# ADCduinoModule.net
KiCad netlist of a schematic drawn in Altium Designer
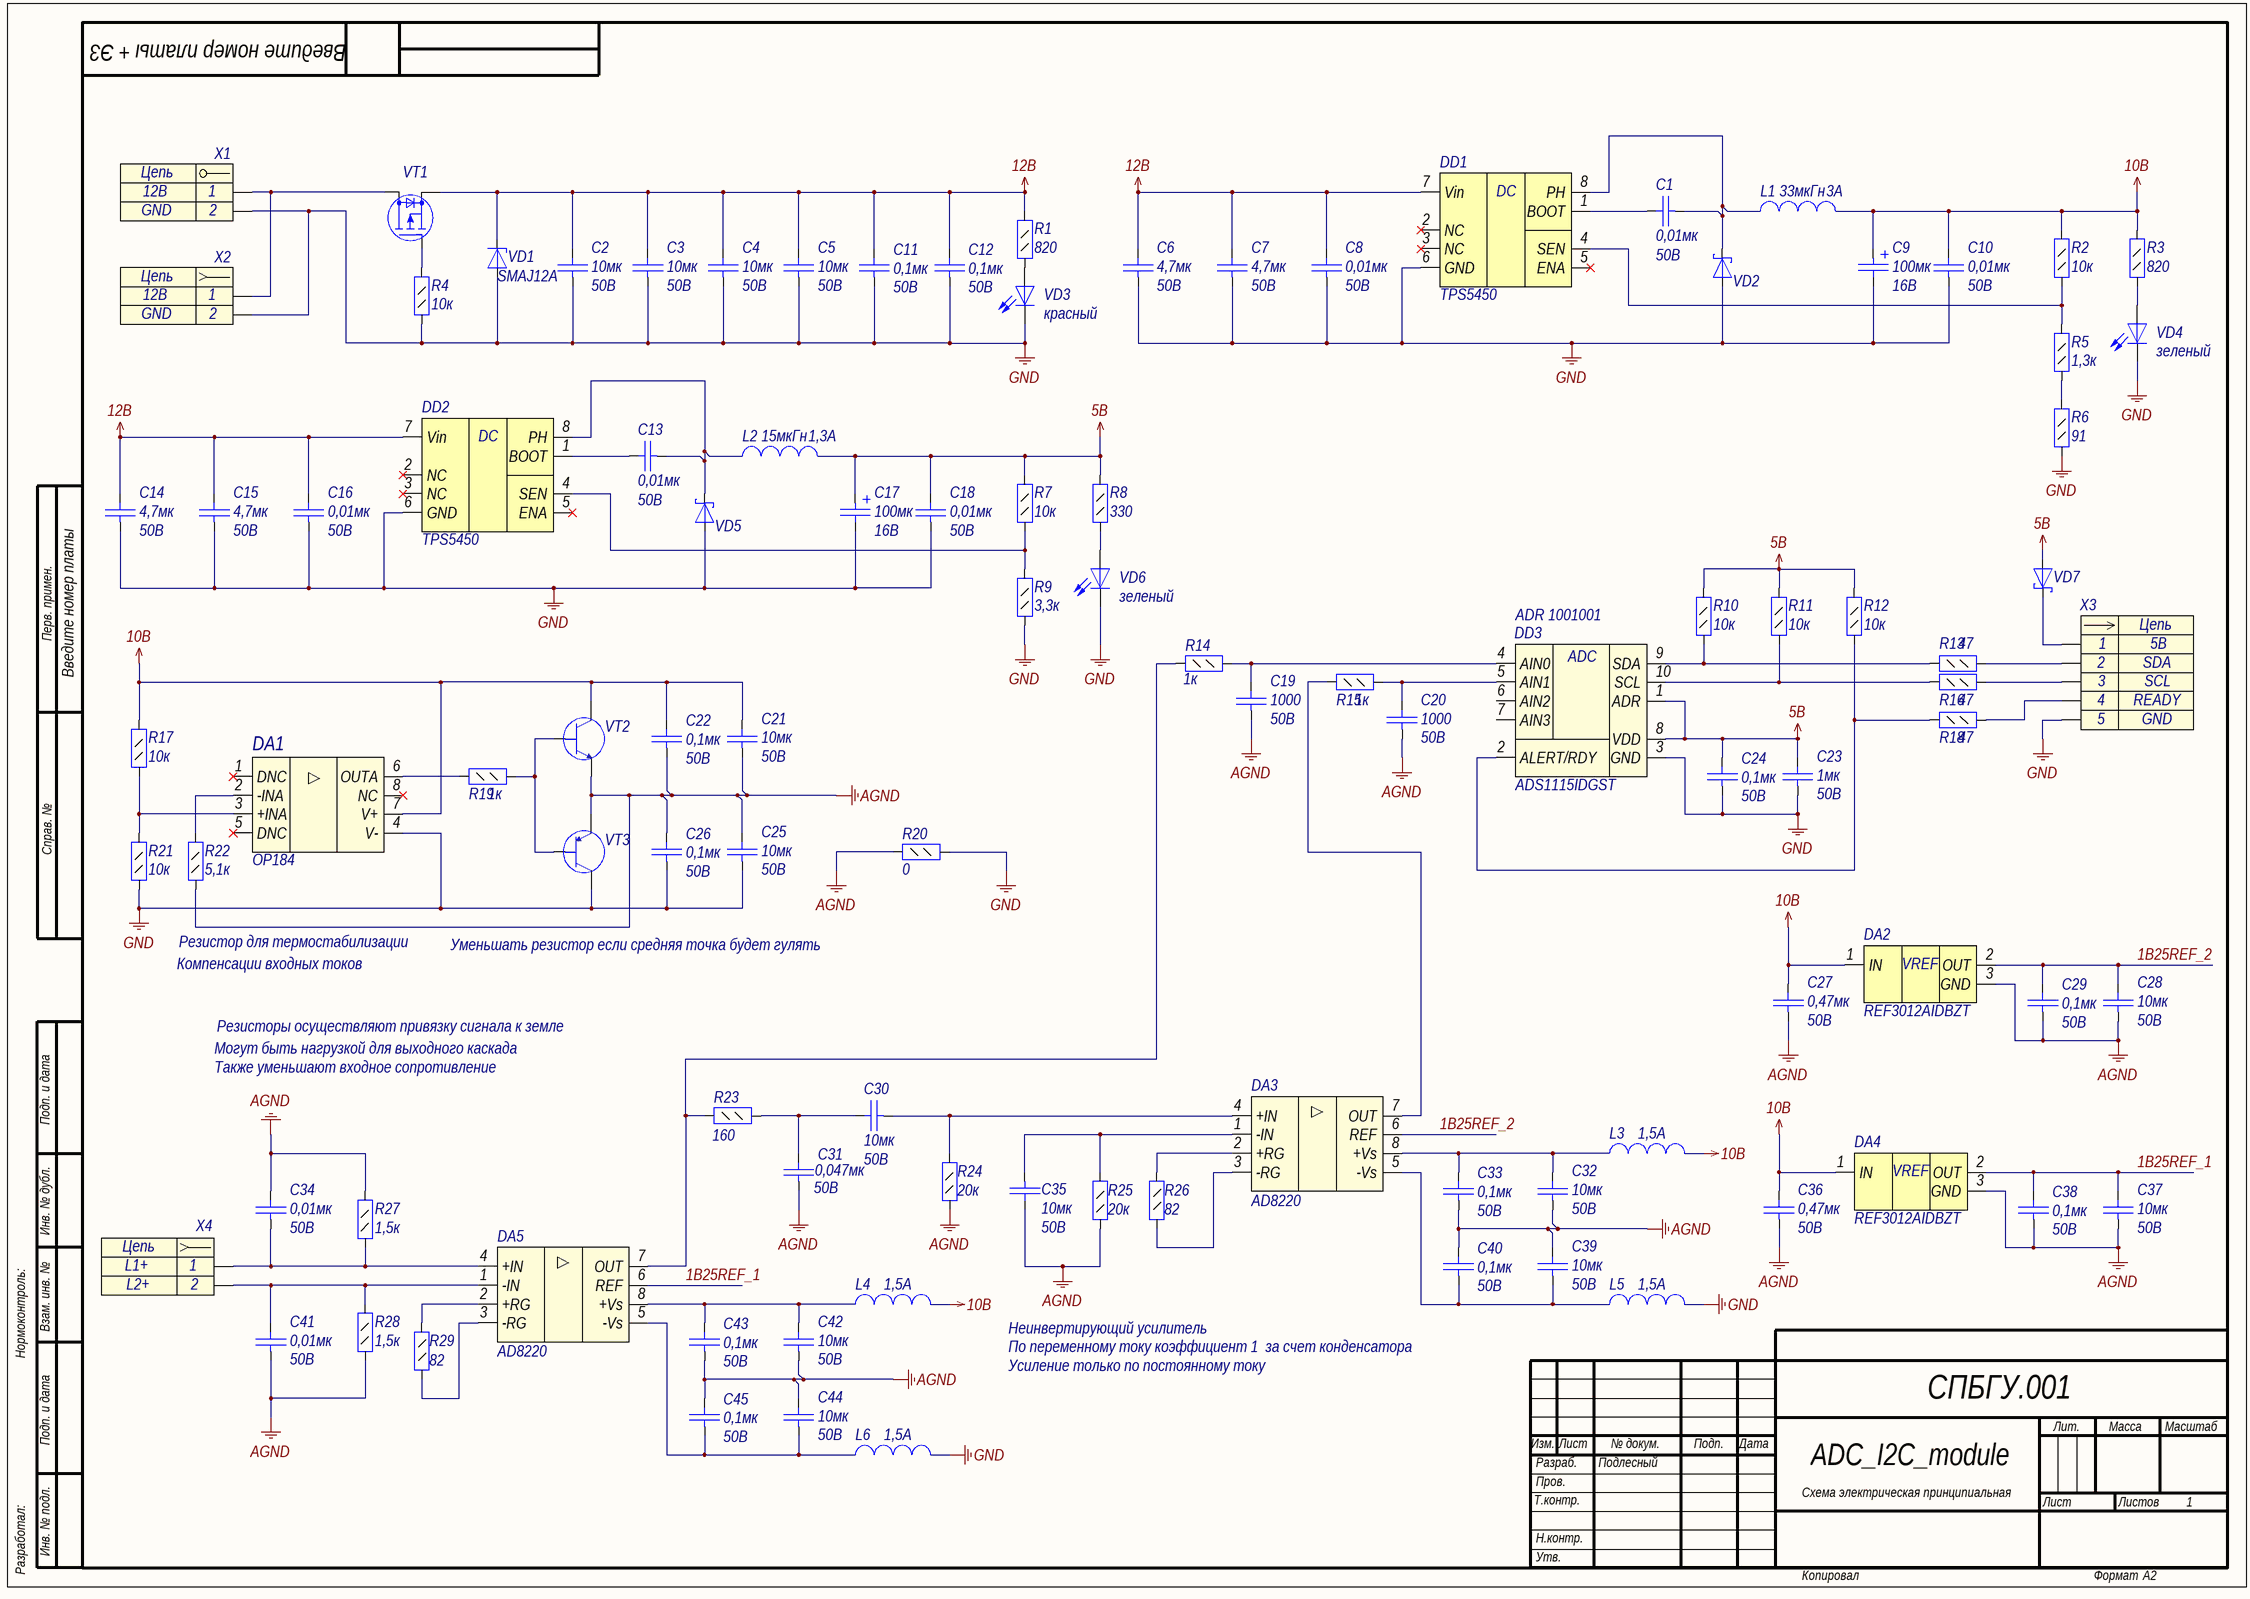
[diagram p0: ADCduinoModule.SchDoc]

(export (version "E")
  (design (tool "Eeschema 10.0.6"))
  (components
    (comp (ref "C1")
      (value "0,01мк")
      (footprint "C0805")
      (description "Конденсатор")
      (fields
        (field (name "VOLTAGE") "50B")
        (field (name "PART NUMBER") "GRM216R71H103K")
        (field (name "Comment") "Capacitor")
      )
      (libsource (lib "MOP44") (part "Capacitor"))
    )
    (comp (ref "C2")
      (value "10мк")
      (footprint "C1210")
      (description "Конденсатор")
      (fields
        (field (name "VOLTAGE") "50В")
        (field (name "PART NUMBER") "GRM32ER71H106K")
        (field (name "Comment") "Capacitor")
      )
      (libsource (lib "MOP44") (part "Capacitor"))
    )
    (comp (ref "C3")
      (value "10мк")
      (footprint "C1210")
      (description "Конденсатор")
      (fields
        (field (name "VOLTAGE") "50В")
        (field (name "PART NUMBER") "GRM32ER71H106K")
        (field (name "Comment") "Capacitor")
      )
      (libsource (lib "MOP44") (part "Capacitor"))
    )
    (comp (ref "C4")
      (value "10мк")
      (footprint "C1210")
      (description "Конденсатор")
      (fields
        (field (name "VOLTAGE") "50В")
        (field (name "PART NUMBER") "GRM32ER71H106K")
        (field (name "Comment") "Capacitor")
      )
      (libsource (lib "MOP44") (part "Capacitor"))
    )
    (comp (ref "C5")
      (value "10мк")
      (footprint "C1210")
      (description "Конденсатор")
      (fields
        (field (name "VOLTAGE") "50В")
        (field (name "PART NUMBER") "GRM32ER71H106K")
        (field (name "Comment") "Capacitor")
      )
      (libsource (lib "MOP44") (part "Capacitor"))
    )
    (comp (ref "C6")
      (value "4,7мк")
      (footprint "C1206")
      (description "Конденсатор")
      (fields
        (field (name "VOLTAGE") "50В")
        (field (name "PART NUMBER") "GRM31CR71H475KA12L")
        (field (name "Comment") "Capacitor")
      )
      (libsource (lib "MOP44") (part "Capacitor"))
    )
    (comp (ref "C7")
      (value "4,7мк")
      (footprint "C1206")
      (description "Конденсатор")
      (fields
        (field (name "VOLTAGE") "50В")
        (field (name "PART NUMBER") "GRM31CR71H475KA12L")
        (field (name "Comment") "Capacitor")
      )
      (libsource (lib "MOP44") (part "Capacitor"))
    )
    (comp (ref "C8")
      (value "0,01мк")
      (footprint "C0805")
      (description "Конденсатор")
      (fields
        (field (name "VOLTAGE") "50B")
        (field (name "PART NUMBER") "GRM216R71H103K")
        (field (name "Comment") "Capacitor")
      )
      (libsource (lib "MOP44") (part "Capacitor"))
    )
    (comp (ref "C9")
      (value "100мк")
      (footprint "TANTAL CASE D")
      (description "Конденсатор полярный")
      (fields
        (field (name "VOLTAGE") "16В")
        (field (name "PART NUMBER") "293D107X9016D2TE3")
        (field (name "Comment") "Capacitor_pol")
      )
      (libsource (lib "MOP44") (part "Capacitor_pol"))
    )
    (comp (ref "C10")
      (value "0,01мк")
      (footprint "C0805")
      (description "Конденсатор")
      (fields
        (field (name "VOLTAGE") "50B")
        (field (name "PART NUMBER") "GRM216R71H103K")
        (field (name "Comment") "Capacitor")
      )
      (libsource (lib "MOP44") (part "Capacitor"))
    )
    (comp (ref "C11")
      (value "0,1мк")
      (footprint "C0805")
      (description "Конденсатор")
      (fields
        (field (name "VOLTAGE") "50B")
        (field (name "PART NUMBER") "GRM21BR71H104K**")
        (field (name "Comment") "Capacitor")
      )
      (libsource (lib "MOP44") (part "Capacitor"))
    )
    (comp (ref "C12")
      (value "0,1мк")
      (footprint "C0805")
      (description "Конденсатор")
      (fields
        (field (name "VOLTAGE") "50B")
        (field (name "PART NUMBER") "GRM21BR71H104K**")
        (field (name "Comment") "Capacitor")
      )
      (libsource (lib "MOP44") (part "Capacitor"))
    )
    (comp (ref "C13")
      (value "0,01мк")
      (footprint "C0805")
      (description "Конденсатор")
      (fields
        (field (name "VOLTAGE") "50B")
        (field (name "PART NUMBER") "GRM216R71H103K")
        (field (name "Comment") "Capacitor")
      )
      (libsource (lib "MOP44") (part "Capacitor"))
    )
    (comp (ref "C14")
      (value "4,7мк")
      (footprint "C1206")
      (description "Конденсатор")
      (fields
        (field (name "VOLTAGE") "50В")
        (field (name "PART NUMBER") "GRM31CR71H475KA12L")
        (field (name "Comment") "Capacitor")
      )
      (libsource (lib "MOP44") (part "Capacitor"))
    )
    (comp (ref "C15")
      (value "4,7мк")
      (footprint "C1206")
      (description "Конденсатор")
      (fields
        (field (name "VOLTAGE") "50В")
        (field (name "PART NUMBER") "GRM31CR71H475KA12L")
        (field (name "Comment") "Capacitor")
      )
      (libsource (lib "MOP44") (part "Capacitor"))
    )
    (comp (ref "C16")
      (value "0,01мк")
      (footprint "C0805")
      (description "Конденсатор")
      (fields
        (field (name "VOLTAGE") "50B")
        (field (name "PART NUMBER") "GRM216R71H103K")
        (field (name "Comment") "Capacitor")
      )
      (libsource (lib "MOP44") (part "Capacitor"))
    )
    (comp (ref "C17")
      (value "100мк")
      (footprint "TANTAL CASE D")
      (description "Конденсатор полярный")
      (fields
        (field (name "VOLTAGE") "16В")
        (field (name "PART NUMBER") "293D107X9016D2TE3")
        (field (name "Comment") "Capacitor_pol")
      )
      (libsource (lib "MOP44") (part "Capacitor_pol"))
    )
    (comp (ref "C18")
      (value "0,01мк")
      (footprint "C0805")
      (description "Конденсатор")
      (fields
        (field (name "VOLTAGE") "50B")
        (field (name "PART NUMBER") "GRM216R71H103K")
        (field (name "Comment") "Capacitor")
      )
      (libsource (lib "MOP44") (part "Capacitor"))
    )
    (comp (ref "C19")
      (value "1000")
      (footprint "C0805")
      (description "Конденсатор")
      (fields
        (field (name "VOLTAGE") "50В")
        (field (name "PART NUMBER") "GRM216R71H102K*")
        (field (name "Comment") "Capacitor")
      )
      (libsource (lib "MOP44") (part "Capacitor"))
    )
    (comp (ref "C20")
      (value "1000")
      (footprint "C0805")
      (description "Конденсатор")
      (fields
        (field (name "VOLTAGE") "50В")
        (field (name "PART NUMBER") "GRM216R71H102K*")
        (field (name "Comment") "Capacitor")
      )
      (libsource (lib "MOP44") (part "Capacitor"))
    )
    (comp (ref "C21")
      (value "10мк")
      (footprint "C1210")
      (description "Конденсатор")
      (fields
        (field (name "VOLTAGE") "50В")
        (field (name "PART NUMBER") "GRM32ER71H106K")
        (field (name "Comment") "Capacitor")
      )
      (libsource (lib "MOP44") (part "Capacitor"))
    )
    (comp (ref "C22")
      (value "0,1мк")
      (footprint "C0805")
      (description "Конденсатор")
      (fields
        (field (name "VOLTAGE") "50B")
        (field (name "PART NUMBER") "GRM21BR71H104K**")
        (field (name "Comment") "Capacitor")
      )
      (libsource (lib "MOP44") (part "Capacitor"))
    )
    (comp (ref "C23")
      (value "1мк")
      (footprint "C0805")
      (description "Конденсатор")
      (fields
        (field (name "VOLTAGE") "50B")
        (field (name "PART NUMBER") "GRM21BR71H105K")
        (field (name "Comment") "Capacitor")
      )
      (libsource (lib "MOP44") (part "Capacitor"))
    )
    (comp (ref "C24")
      (value "0,1мк")
      (footprint "C0805")
      (description "Конденсатор")
      (fields
        (field (name "VOLTAGE") "50B")
        (field (name "PART NUMBER") "GRM21BR71H104K**")
        (field (name "Comment") "Capacitor")
      )
      (libsource (lib "MOP44") (part "Capacitor"))
    )
    (comp (ref "C25")
      (value "10мк")
      (footprint "C1210")
      (description "Конденсатор")
      (fields
        (field (name "VOLTAGE") "50В")
        (field (name "PART NUMBER") "GRM32ER71H106K")
        (field (name "Comment") "Capacitor")
      )
      (libsource (lib "MOP44") (part "Capacitor"))
    )
    (comp (ref "C26")
      (value "0,1мк")
      (footprint "C0805")
      (description "Конденсатор")
      (fields
        (field (name "VOLTAGE") "50B")
        (field (name "PART NUMBER") "GRM21BR71H104K**")
        (field (name "Comment") "Capacitor")
      )
      (libsource (lib "MOP44") (part "Capacitor"))
    )
    (comp (ref "C27")
      (value "0,47мк")
      (footprint "C0805")
      (description "Конденсатор")
      (fields
        (field (name "VOLTAGE") "50B")
        (field (name "PART NUMBER") "GRM219R71C474K")
        (field (name "Comment") "Capacitor")
      )
      (libsource (lib "MOP44") (part "Capacitor"))
    )
    (comp (ref "C28")
      (value "10мк")
      (footprint "C1210")
      (description "Конденсатор")
      (fields
        (field (name "VOLTAGE") "50В")
        (field (name "PART NUMBER") "GRM32ER71H106K")
        (field (name "Comment") "Capacitor")
      )
      (libsource (lib "MOP44") (part "Capacitor"))
    )
    (comp (ref "C29")
      (value "0,1мк")
      (footprint "C0805")
      (description "Конденсатор")
      (fields
        (field (name "VOLTAGE") "50B")
        (field (name "PART NUMBER") "GRM21BR71H104K**")
        (field (name "Comment") "Capacitor")
      )
      (libsource (lib "MOP44") (part "Capacitor"))
    )
    (comp (ref "C30")
      (value "10мк")
      (footprint "C1210")
      (description "Конденсатор")
      (fields
        (field (name "VOLTAGE") "50В")
        (field (name "PART NUMBER") "GRM32ER71H106K")
        (field (name "Comment") "Capacitor")
      )
      (libsource (lib "MOP44") (part "Capacitor"))
    )
    (comp (ref "C31")
      (value "0,047мк")
      (footprint "C0805")
      (description "Конденсатор")
      (fields
        (field (name "VOLTAGE") "50B")
        (field (name "PART NUMBER") "GRM21BR71H473K")
        (field (name "Comment") "Capacitor")
      )
      (libsource (lib "MOP44") (part "Capacitor"))
    )
    (comp (ref "C32")
      (value "10мк")
      (footprint "C1210")
      (description "Конденсатор")
      (fields
        (field (name "VOLTAGE") "50В")
        (field (name "PART NUMBER") "GRM32ER71H106K")
        (field (name "Comment") "Capacitor")
      )
      (libsource (lib "MOP44") (part "Capacitor"))
    )
    (comp (ref "C33")
      (value "0,1мк")
      (footprint "C0805")
      (description "Конденсатор")
      (fields
        (field (name "VOLTAGE") "50B")
        (field (name "PART NUMBER") "GRM21BR71H104K**")
        (field (name "Comment") "Capacitor")
      )
      (libsource (lib "MOP44") (part "Capacitor"))
    )
    (comp (ref "C34")
      (value "0,01мк")
      (footprint "C0805")
      (description "Конденсатор")
      (fields
        (field (name "VOLTAGE") "50B")
        (field (name "PART NUMBER") "GRM216R71H103K")
        (field (name "Comment") "Capacitor")
      )
      (libsource (lib "MOP44") (part "Capacitor"))
    )
    (comp (ref "C35")
      (value "10мк")
      (footprint "C1210")
      (description "Конденсатор")
      (fields
        (field (name "VOLTAGE") "50В")
        (field (name "PART NUMBER") "GRM32ER71H106K")
        (field (name "Comment") "Capacitor")
      )
      (libsource (lib "MOP44") (part "Capacitor"))
    )
    (comp (ref "C36")
      (value "0,47мк")
      (footprint "C0805")
      (description "Конденсатор")
      (fields
        (field (name "VOLTAGE") "50B")
        (field (name "PART NUMBER") "GRM219R71C474K")
        (field (name "Comment") "Capacitor")
      )
      (libsource (lib "MOP44") (part "Capacitor"))
    )
    (comp (ref "C37")
      (value "10мк")
      (footprint "C1210")
      (description "Конденсатор")
      (fields
        (field (name "VOLTAGE") "50В")
        (field (name "PART NUMBER") "GRM32ER71H106K")
        (field (name "Comment") "Capacitor")
      )
      (libsource (lib "MOP44") (part "Capacitor"))
    )
    (comp (ref "C38")
      (value "0,1мк")
      (footprint "C0805")
      (description "Конденсатор")
      (fields
        (field (name "VOLTAGE") "50B")
        (field (name "PART NUMBER") "GRM21BR71H104K**")
        (field (name "Comment") "Capacitor")
      )
      (libsource (lib "MOP44") (part "Capacitor"))
    )
    (comp (ref "C39")
      (value "10мк")
      (footprint "C1210")
      (description "Конденсатор")
      (fields
        (field (name "VOLTAGE") "50В")
        (field (name "PART NUMBER") "GRM32ER71H106K")
        (field (name "Comment") "Capacitor")
      )
      (libsource (lib "MOP44") (part "Capacitor"))
    )
    (comp (ref "C40")
      (value "0,1мк")
      (footprint "C0805")
      (description "Конденсатор")
      (fields
        (field (name "VOLTAGE") "50B")
        (field (name "PART NUMBER") "GRM21BR71H104K**")
        (field (name "Comment") "Capacitor")
      )
      (libsource (lib "MOP44") (part "Capacitor"))
    )
    (comp (ref "C41")
      (value "0,01мк")
      (footprint "C0805")
      (description "Конденсатор")
      (fields
        (field (name "VOLTAGE") "50B")
        (field (name "PART NUMBER") "GRM216R71H103K")
        (field (name "Comment") "Capacitor")
      )
      (libsource (lib "MOP44") (part "Capacitor"))
    )
    (comp (ref "C42")
      (value "10мк")
      (footprint "C1210")
      (description "Конденсатор")
      (fields
        (field (name "VOLTAGE") "50В")
        (field (name "PART NUMBER") "GRM32ER71H106K")
        (field (name "Comment") "Capacitor")
      )
      (libsource (lib "MOP44") (part "Capacitor"))
    )
    (comp (ref "C43")
      (value "0,1мк")
      (footprint "C0805")
      (description "Конденсатор")
      (fields
        (field (name "VOLTAGE") "50B")
        (field (name "PART NUMBER") "GRM21BR71H104K**")
        (field (name "Comment") "Capacitor")
      )
      (libsource (lib "MOP44") (part "Capacitor"))
    )
    (comp (ref "C44")
      (value "10мк")
      (footprint "C1210")
      (description "Конденсатор")
      (fields
        (field (name "VOLTAGE") "50В")
        (field (name "PART NUMBER") "GRM32ER71H106K")
        (field (name "Comment") "Capacitor")
      )
      (libsource (lib "MOP44") (part "Capacitor"))
    )
    (comp (ref "C45")
      (value "0,1мк")
      (footprint "C0805")
      (description "Конденсатор")
      (fields
        (field (name "VOLTAGE") "50B")
        (field (name "PART NUMBER") "GRM21BR71H104K**")
        (field (name "Comment") "Capacitor")
      )
      (libsource (lib "MOP44") (part "Capacitor"))
    )
    (comp (ref "DA1")
      (value "OP184")
      (footprint "SO8")
      (description "Precision Rail-to-Rail\r\nInput and Output Operational Amplifiers")
      (fields (field (name "PART NUMBER") "OP184ESZ"))
      (libsource (lib "MOP44") (part "OP184"))
    )
    (comp (ref "DA2")
      (value "REF30xx")
      (footprint "SOT23-3")
      (description "CMOS Voltage Reference")
      (fields (field (name "PART NUMBER") "REF3012AIDBZT") (field (name "MANUFACTURER") "Texas Instruments"))
      (libsource (lib "MOP44") (part "REF30xx"))
    )
    (comp (ref "DA3")
      (value "AD8220")
      (footprint "MSOP8")
      (description "JFET Input Instrumentation Amplifier")
      (fields (field (name "PART NUMBER") "AD8220ARMZ"))
      (libsource (lib "MOP44") (part "AD8220"))
    )
    (comp (ref "DA4")
      (value "REF30xx")
      (footprint "SOT23-3")
      (description "CMOS Voltage Reference")
      (fields (field (name "PART NUMBER") "REF3012AIDBZT") (field (name "MANUFACTURER") "Texas Instruments"))
      (libsource (lib "MOP44") (part "REF30xx"))
    )
    (comp (ref "DA5")
      (value "AD8220")
      (footprint "MSOP8")
      (description "JFET Input Instrumentation Amplifier")
      (fields (field (name "PART NUMBER") "AD8220ARMZ"))
      (libsource (lib "MOP44") (part "AD8220"))
    )
    (comp (ref "DD1")
      (value "TPS5450")
      (footprint "SO Powerpad8")
      (description "5-A, Wide Input Range, Step-Down Converter")
      (fields (field (name "MANUFACTURER") "Texas Instruments"))
      (libsource (lib "MOP44") (part "TPS5450"))
    )
    (comp (ref "DD2")
      (value "TPS5450")
      (footprint "SO Powerpad8")
      (description "5-A, Wide Input Range, Step-Down Converter")
      (fields (field (name "MANUFACTURER") "Texas Instruments"))
      (libsource (lib "MOP44") (part "TPS5450"))
    )
    (comp (ref "DD3")
      (value "ADS1115IDGST")
      (footprint "MSOP10")
      (description "Ultra-Small, Low-Power, 16-Bit  Analog-to-Digital Converter with Internal Reference")
      (libsource (lib "MOP44") (part "ADS1115IDGST"))
    )
    (comp (ref "L1")
      (value "33мкГн")
      (footprint "IND_12.8x12.8")
      (description "EMI Suppression Filter")
      (fields
        (field (name "RATED CURRENT") "3A")
        (field (name "PART NUMBER") "B82477G4333M000")
        (field (name "Comment") "Inductor")
      )
      (libsource (lib "MOP44") (part "Inductor"))
    )
    (comp (ref "L2")
      (value "15мкГн")
      (footprint "SDR0604")
      (description "EMI Suppression Filter")
      (fields
        (field (name "RATED CURRENT") "1,3A")
        (field (name "PART NUMBER") "SDR0604- 150YL")
        (field (name "Comment") "Inductor")
      )
      (libsource (lib "MOP44") (part "Inductor"))
    )
    (comp (ref "L3")
      (value "Inductor")
      (footprint "L0603")
      (description "EMI Suppression Filter")
      (fields (field (name "RATED CURRENT") "1,5A") (field (name "PART NUMBER") "BLM18PG181SN1D"))
      (libsource (lib "MOP44") (part "Inductor"))
    )
    (comp (ref "L4")
      (value "Inductor")
      (footprint "L0603")
      (description "EMI Suppression Filter")
      (fields (field (name "RATED CURRENT") "1,5A") (field (name "PART NUMBER") "BLM18PG181SN1D"))
      (libsource (lib "MOP44") (part "Inductor"))
    )
    (comp (ref "L5")
      (value "Inductor")
      (footprint "L0603")
      (description "EMI Suppression Filter")
      (fields (field (name "RATED CURRENT") "1,5A") (field (name "PART NUMBER") "BLM18PG181SN1D"))
      (libsource (lib "MOP44") (part "Inductor"))
    )
    (comp (ref "L6")
      (value "Inductor")
      (footprint "L0603")
      (description "EMI Suppression Filter")
      (fields (field (name "RATED CURRENT") "1,5A") (field (name "PART NUMBER") "BLM18PG181SN1D"))
      (libsource (lib "MOP44") (part "Inductor"))
    )
    (comp (ref "R1")
      (value "820")
      (footprint "R0805")
      (description "Резистор")
      (fields (field (name "PART NUMBER") "RC0805FR-07820RL") (field (name "POWER") "0,125Вт"))
      (libsource (lib "MOP44") (part "Resistor_0,125Вт"))
    )
    (comp (ref "R2")
      (value "10к")
      (footprint "R0805")
      (description "Резистор")
      (fields (field (name "PART NUMBER") "RC0805FR-0710KL") (field (name "POWER") "0,125Вт"))
      (libsource (lib "MOP44") (part "Resistor_0,125Вт"))
    )
    (comp (ref "R3")
      (value "820")
      (footprint "R0805")
      (description "Резистор")
      (fields (field (name "PART NUMBER") "RC0805FR-07820RL") (field (name "POWER") "0,125Вт"))
      (libsource (lib "MOP44") (part "Resistor_0,125Вт"))
    )
    (comp (ref "R4")
      (value "10к")
      (footprint "R0805")
      (description "Резистор")
      (fields (field (name "PART NUMBER") "RC0805FR-0710KL") (field (name "POWER") "0,125Вт"))
      (libsource (lib "MOP44") (part "Resistor_0,125Вт"))
    )
    (comp (ref "R5")
      (value "1,3к")
      (footprint "R0805")
      (description "Резистор")
      (fields (field (name "PART NUMBER") "RC0805FR-071K3") (field (name "POWER") "0,125Вт"))
      (libsource (lib "MOP44") (part "Resistor_0,125Вт"))
    )
    (comp (ref "R6")
      (value "91")
      (footprint "R0805")
      (description "Резистор")
      (fields (field (name "PART NUMBER") "RC0805FR-0791RL") (field (name "POWER") "0,125Вт"))
      (libsource (lib "MOP44") (part "Resistor_0,125Вт"))
    )
    (comp (ref "R7")
      (value "10к")
      (footprint "R0805")
      (description "Резистор")
      (fields (field (name "PART NUMBER") "RC0805FR-0710KL") (field (name "POWER") "0,125Вт"))
      (libsource (lib "MOP44") (part "Resistor_0,125Вт"))
    )
    (comp (ref "R8")
      (value "330")
      (footprint "R0805")
      (description "Резистор")
      (fields (field (name "PART NUMBER") "RC0805FR-07330RL") (field (name "POWER") "0,125Вт"))
      (libsource (lib "MOP44") (part "Resistor_0,125Вт"))
    )
    (comp (ref "R9")
      (value "3,3к")
      (footprint "R0805")
      (description "Резистор")
      (fields (field (name "PART NUMBER") "RC0805FR-072K3") (field (name "POWER") "0,125Вт"))
      (libsource (lib "MOP44") (part "Resistor_0,125Вт"))
    )
    (comp (ref "R10")
      (value "10к")
      (footprint "R0805")
      (description "Резистор")
      (fields (field (name "PART NUMBER") "RC0805FR-0710KL") (field (name "POWER") "0,125Вт"))
      (libsource (lib "MOP44") (part "Resistor_0,125Вт"))
    )
    (comp (ref "R11")
      (value "10к")
      (footprint "R0805")
      (description "Резистор")
      (fields (field (name "PART NUMBER") "RC0805FR-0710KL") (field (name "POWER") "0,125Вт"))
      (libsource (lib "MOP44") (part "Resistor_0,125Вт"))
    )
    (comp (ref "R12")
      (value "10к")
      (footprint "R0805")
      (description "Резистор")
      (fields (field (name "PART NUMBER") "RC0805FR-0710KL") (field (name "POWER") "0,125Вт"))
      (libsource (lib "MOP44") (part "Resistor_0,125Вт"))
    )
    (comp (ref "R13")
      (value "47")
      (footprint "R0805")
      (description "Резистор")
      (fields (field (name "PART NUMBER") "RC0805FR-0747RL") (field (name "POWER") "0,125Вт"))
      (libsource (lib "") (part "Resistor_0,125Вт_1"))
    )
    (comp (ref "R14")
      (value "1к")
      (footprint "R0805")
      (description "Резистор")
      (fields (field (name "PART NUMBER") "RC0805FR-071KL") (field (name "POWER") "0,125Вт"))
      (libsource (lib "") (part "Resistor_0,125Вт_1"))
    )
    (comp (ref "R15")
      (value "1к")
      (footprint "R0805")
      (description "Резистор")
      (fields (field (name "PART NUMBER") "RC0805FR-071KL") (field (name "POWER") "0,125Вт"))
      (libsource (lib "") (part "Resistor_0,125Вт_1"))
    )
    (comp (ref "R16")
      (value "47")
      (footprint "R0805")
      (description "Резистор")
      (fields (field (name "PART NUMBER") "RC0805FR-0747RL") (field (name "POWER") "0,125Вт"))
      (libsource (lib "") (part "Resistor_0,125Вт_1"))
    )
    (comp (ref "R17")
      (value "10к")
      (footprint "R0805")
      (description "Резистор")
      (fields (field (name "PART NUMBER") "RC0805FR-0710KL") (field (name "POWER") "0,125Вт"))
      (libsource (lib "MOP44") (part "Resistor_0,125Вт"))
    )
    (comp (ref "R18")
      (value "47")
      (footprint "R0805")
      (description "Резистор")
      (fields (field (name "PART NUMBER") "RC0805FR-0747RL") (field (name "POWER") "0,125Вт"))
      (libsource (lib "") (part "Resistor_0,125Вт_1"))
    )
    (comp (ref "R19")
      (value "1к")
      (footprint "R0805")
      (description "Резистор")
      (fields (field (name "PART NUMBER") "RC0805FR-071KL") (field (name "POWER") "0,125Вт"))
      (libsource (lib "") (part "Resistor_0,125Вт_1"))
    )
    (comp (ref "R20")
      (value "0")
      (footprint "R0805")
      (description "Резистор")
      (fields (field (name "PART NUMBER") "RC0805FR-070RL") (field (name "POWER") "0,125Вт"))
      (libsource (lib "") (part "Resistor_0,125Вт_1"))
    )
    (comp (ref "R21")
      (value "10к")
      (footprint "R0805")
      (description "Резистор")
      (fields (field (name "PART NUMBER") "RC0805FR-0710KL") (field (name "POWER") "0,125Вт"))
      (libsource (lib "MOP44") (part "Resistor_0,125Вт"))
    )
    (comp (ref "R22")
      (value "5,1к")
      (footprint "R0805")
      (description "Резистор")
      (fields (field (name "PART NUMBER") "RC0805FR-075K1") (field (name "POWER") "0,125Вт"))
      (libsource (lib "MOP44") (part "Resistor_0,125Вт"))
    )
    (comp (ref "R23")
      (value "160")
      (footprint "R0805")
      (description "Резистор")
      (fields (field (name "PART NUMBER") "RC0805FR-07160RL") (field (name "POWER") "0,125Вт"))
      (libsource (lib "") (part "Resistor_0,125Вт_1"))
    )
    (comp (ref "R24")
      (value "20к")
      (footprint "R0805")
      (description "Резистор")
      (fields (field (name "PART NUMBER") "RC0805FR-0720KL") (field (name "POWER") "0,125Вт"))
      (libsource (lib "MOP44") (part "Resistor_0,125Вт"))
    )
    (comp (ref "R25")
      (value "20к")
      (footprint "R0805")
      (description "Резистор")
      (fields (field (name "PART NUMBER") "RC0805FR-0720KL") (field (name "POWER") "0,125Вт"))
      (libsource (lib "MOP44") (part "Resistor_0,125Вт"))
    )
    (comp (ref "R26")
      (value "82")
      (footprint "R0805")
      (description "Резистор")
      (fields (field (name "PART NUMBER") "RC0805FR-0782RL") (field (name "POWER") "0,125Вт"))
      (libsource (lib "") (part "Resistor_0,125Вт_2"))
    )
    (comp (ref "R27")
      (value "1,5к")
      (footprint "R0805")
      (description "Резистор")
      (fields (field (name "PART NUMBER") "RC0805FR-071K5") (field (name "POWER") "0,125Вт"))
      (libsource (lib "MOP44") (part "Resistor_0,125Вт"))
    )
    (comp (ref "R28")
      (value "1,5к")
      (footprint "R0805")
      (description "Резистор")
      (fields (field (name "PART NUMBER") "RC0805FR-071K5") (field (name "POWER") "0,125Вт"))
      (libsource (lib "MOP44") (part "Resistor_0,125Вт"))
    )
    (comp (ref "R29")
      (value "82")
      (footprint "R0805")
      (description "Резистор")
      (fields (field (name "PART NUMBER") "RC0805FR-0782RL") (field (name "POWER") "0,125Вт"))
      (libsource (lib "") (part "Resistor_0,125Вт_2"))
    )
    (comp (ref "VD1")
      (value "DiodeZener")
      (footprint "SMA")
      (description "Cтабилитрон (лавинный выпрямительный диод) односторонний")
      (fields (field (name "PART NUMBER") "SMAJ12A"))
      (libsource (lib "MOP44") (part "DiodeZener"))
    )
    (comp (ref "VD2")
      (value "DiodeSchottky")
      (footprint "SMA")
      (description "Диод Шоттки")
      (fields (field (name "PART NUMBER") "SK34A"))
      (libsource (lib "MOP44") (part "DiodeSchottky"))
    )
    (comp (ref "VD3")
      (value "красный")
      (footprint "L_0805")
      (description "Светодиод")
      (fields (field (name "PART NUMBER") "KP-2012EC"))
      (libsource (lib "MOP44") (part "LED"))
    )
    (comp (ref "VD4")
      (value "зеленый")
      (footprint "L_0805")
      (description "Светодиод")
      (fields (field (name "PART NUMBER") "KP-2012MGC"))
      (libsource (lib "MOP44") (part "LED"))
    )
    (comp (ref "VD5")
      (value "DiodeSchottky")
      (footprint "SMA")
      (description "Диод Шоттки")
      (fields (field (name "PART NUMBER") "SK34A"))
      (libsource (lib "MOP44") (part "DiodeSchottky"))
    )
    (comp (ref "VD6")
      (value "зеленый")
      (footprint "L_0805")
      (description "Светодиод")
      (fields (field (name "PART NUMBER") "KP-2012MGC"))
      (libsource (lib "MOP44") (part "LED"))
    )
    (comp (ref "VD7")
      (value "DiodeSchottky")
      (footprint "SMA")
      (description "Диод Шоттки")
      (fields (field (name "PART NUMBER") "SK34A"))
      (libsource (lib "MOP44") (part "DiodeSchottky"))
    )
    (comp (ref "VT1")
      (value "P-MOSFET")
      (footprint "DPAK")
      (description "N-MOSFET")
      (fields (field (name "PART NUMBER") "FDD6637") (field (name "MANUFACTURER") "Fairchild Semiconductor"))
      (libsource (lib "MOP44") (part "P-MOSFET"))
    )
    (comp (ref "VT2")
      (value "BJT NPN")
      (footprint "SOT-223")
      (fields (field (name "POWER") "2Вт") (field (name "PART NUMBER") "PBSS4540Z.115"))
      (libsource (lib "MOP44") (part "BJT NPN"))
    )
    (comp (ref "VT3")
      (value "BJT PNP")
      (footprint "SOT-223")
      (fields (field (name "POWER") "2Вт") (field (name "PART NUMBER") "PBSS5540Z.115"))
      (libsource (lib "MOP44") (part "BJT PNP"))
    )
    (comp (ref "X1")
      (value "Header_2_trm")
      (footprint "TERMINAL-2WAY-3.5MM")
      (description "Разъем - 2 конт. клеммник")
      (libsource (lib "MOP44") (part "Header_2_trm"))
    )
    (comp (ref "X2")
      (value "Header_2_sct")
      (footprint "DS-210")
      (description "Разъем - 2 конт. розетка")
      (fields (field (name "PART NUMBER") "DS-210B(PBT)(NB)"))
      (libsource (lib "MOP44") (part "Header_2_sct"))
    )
    (comp (ref "X3")
      (value "Header_5_plg")
      (footprint "PLS-5")
      (description "Разъем - 5 конт. вилка")
      (fields (field (name "PART NUMBER") "DS1021-1*5SF112-B"))
      (libsource (lib "MOP44") (part "Header_5_plg"))
    )
    (comp (ref "X4")
      (value "Header_2_sct")
      (footprint "TAB_2PAD")
      (description "Разъем - 2 конт. розетка")
      (libsource (lib "MOP44") (part "Header_2_sct"))
    )
  )
  (nets
    (net (code "1") (name "/1B25REF_1") (class "Default")
      (node (ref "C37") (pin "2") (pinfunction "2_2") (pintype "passive"))
      (node (ref "C38") (pin "2") (pinfunction "2_2") (pintype "passive"))
      (node (ref "DA4") (pin "2") (pinfunction "OUT_2") (pintype "passive"))
      (node (ref "DA5") (pin "6") (pinfunction "REF_6") (pintype "passive"))
    )
    (net (code "2") (name "/1B25REF_2") (class "Default")
      (node (ref "C28") (pin "2") (pinfunction "2_2") (pintype "passive"))
      (node (ref "C29") (pin "2") (pinfunction "2_2") (pintype "passive"))
      (node (ref "DA2") (pin "2") (pinfunction "OUT_2") (pintype "passive"))
      (node (ref "DA3") (pin "6") (pinfunction "REF_6") (pintype "passive"))
    )
    (net (code "3") (name "5B") (class "Default")
      (node (ref "C17") (pin "1") (pinfunction "1_1") (pintype "passive"))
      (node (ref "C18") (pin "2") (pinfunction "2_2") (pintype "passive"))
      (node (ref "C23") (pin "2") (pinfunction "2_2") (pintype "passive"))
      (node (ref "C24") (pin "2") (pinfunction "2_2") (pintype "passive"))
      (node (ref "DD3") (pin "1") (pinfunction "ADR_1") (pintype "power_in"))
      (node (ref "DD3") (pin "8") (pinfunction "VDD_8") (pintype "power_in"))
      (node (ref "L2") (pin "2") (pinfunction "2_2") (pintype "passive"))
      (node (ref "R10") (pin "2") (pinfunction "2_2") (pintype "passive"))
      (node (ref "R11") (pin "2") (pinfunction "2_2") (pintype "passive"))
      (node (ref "R12") (pin "2") (pinfunction "2_2") (pintype "passive"))
      (node (ref "R7") (pin "2") (pinfunction "2_2") (pintype "passive"))
      (node (ref "R8") (pin "2") (pinfunction "2_2") (pintype "passive"))
      (node (ref "VD7") (pin "2") (pinfunction "A_2") (pintype "passive"))
    )
    (net (code "4") (name "10B") (class "Default")
      (node (ref "C10") (pin "2") (pinfunction "2_2") (pintype "passive"))
      (node (ref "C21") (pin "2") (pinfunction "2_2") (pintype "passive"))
      (node (ref "C22") (pin "2") (pinfunction "2_2") (pintype "passive"))
      (node (ref "C27") (pin "2") (pinfunction "2_2") (pintype "passive"))
      (node (ref "C36") (pin "2") (pinfunction "2_2") (pintype "passive"))
      (node (ref "C9") (pin "1") (pinfunction "1_1") (pintype "passive"))
      (node (ref "DA1") (pin "7") (pinfunction "V+_7") (pintype "power_in"))
      (node (ref "DA2") (pin "1") (pinfunction "IN_1") (pintype "passive"))
      (node (ref "DA4") (pin "1") (pinfunction "IN_1") (pintype "passive"))
      (node (ref "L1") (pin "2") (pinfunction "2_2") (pintype "passive"))
      (node (ref "L3") (pin "2") (pinfunction "2_2") (pintype "passive"))
      (node (ref "L4") (pin "2") (pinfunction "2_2") (pintype "passive"))
      (node (ref "R17") (pin "2") (pinfunction "2_2") (pintype "passive"))
      (node (ref "R2") (pin "2") (pinfunction "2_2") (pintype "passive"))
      (node (ref "R3") (pin "2") (pinfunction "2_2") (pintype "passive"))
      (node (ref "VT2") (pin "3") (pinfunction "3_3") (pintype "passive"))
    )
    (net (code "5") (name "12B") (class "Default")
      (node (ref "C11") (pin "2") (pinfunction "2_2") (pintype "passive"))
      (node (ref "C12") (pin "2") (pinfunction "2_2") (pintype "passive"))
      (node (ref "C14") (pin "2") (pinfunction "2_2") (pintype "passive"))
      (node (ref "C15") (pin "2") (pinfunction "2_2") (pintype "passive"))
      (node (ref "C16") (pin "2") (pinfunction "2_2") (pintype "passive"))
      (node (ref "C2") (pin "2") (pinfunction "2_2") (pintype "passive"))
      (node (ref "C3") (pin "2") (pinfunction "2_2") (pintype "passive"))
      (node (ref "C4") (pin "2") (pinfunction "2_2") (pintype "passive"))
      (node (ref "C5") (pin "2") (pinfunction "2_2") (pintype "passive"))
      (node (ref "C6") (pin "2") (pinfunction "2_2") (pintype "passive"))
      (node (ref "C7") (pin "2") (pinfunction "2_2") (pintype "passive"))
      (node (ref "C8") (pin "2") (pinfunction "2_2") (pintype "passive"))
      (node (ref "DD1") (pin "7") (pinfunction "Vin_7") (pintype "passive"))
      (node (ref "DD2") (pin "7") (pinfunction "Vin_7") (pintype "passive"))
      (node (ref "R1") (pin "2") (pinfunction "2_2") (pintype "passive"))
      (node (ref "VD1") (pin "1") (pinfunction "K_1") (pintype "passive"))
      (node (ref "VT1") (pin "3") (pinfunction "S_3") (pintype "passive"))
    )
    (net (code "6") (name "AGND") (class "Default")
      (node (ref "C19") (pin "1") (pinfunction "1_1") (pintype "passive"))
      (node (ref "C20") (pin "1") (pinfunction "1_1") (pintype "passive"))
      (node (ref "C21") (pin "1") (pinfunction "1_1") (pintype "passive"))
      (node (ref "C22") (pin "1") (pinfunction "1_1") (pintype "passive"))
      (node (ref "C25") (pin "2") (pinfunction "2_2") (pintype "passive"))
      (node (ref "C26") (pin "2") (pinfunction "2_2") (pintype "passive"))
      (node (ref "C27") (pin "1") (pinfunction "1_1") (pintype "passive"))
      (node (ref "C28") (pin "1") (pinfunction "1_1") (pintype "passive"))
      (node (ref "C29") (pin "1") (pinfunction "1_1") (pintype "passive"))
      (node (ref "C31") (pin "1") (pinfunction "1_1") (pintype "passive"))
      (node (ref "C32") (pin "1") (pinfunction "1_1") (pintype "passive"))
      (node (ref "C33") (pin "1") (pinfunction "1_1") (pintype "passive"))
      (node (ref "C34") (pin "2") (pinfunction "2_2") (pintype "passive"))
      (node (ref "C35") (pin "2") (pinfunction "2_2") (pintype "passive"))
      (node (ref "C36") (pin "1") (pinfunction "1_1") (pintype "passive"))
      (node (ref "C37") (pin "1") (pinfunction "1_1") (pintype "passive"))
      (node (ref "C38") (pin "1") (pinfunction "1_1") (pintype "passive"))
      (node (ref "C39") (pin "2") (pinfunction "2_2") (pintype "passive"))
      (node (ref "C40") (pin "2") (pinfunction "2_2") (pintype "passive"))
      (node (ref "C41") (pin "1") (pinfunction "1_1") (pintype "passive"))
      (node (ref "C42") (pin "1") (pinfunction "1_1") (pintype "passive"))
      (node (ref "C43") (pin "1") (pinfunction "1_1") (pintype "passive"))
      (node (ref "C44") (pin "2") (pinfunction "2_2") (pintype "passive"))
      (node (ref "C45") (pin "2") (pinfunction "2_2") (pintype "passive"))
      (node (ref "DA2") (pin "3") (pinfunction "GND_3") (pintype "passive"))
      (node (ref "DA4") (pin "3") (pinfunction "GND_3") (pintype "passive"))
      (node (ref "R20") (pin "1") (pinfunction "1_1") (pintype "passive"))
      (node (ref "R22") (pin "1") (pinfunction "1_1") (pintype "passive"))
      (node (ref "R24") (pin "1") (pinfunction "1_1") (pintype "passive"))
      (node (ref "R25") (pin "1") (pinfunction "1_1") (pintype "passive"))
      (node (ref "R27") (pin "2") (pinfunction "2_2") (pintype "passive"))
      (node (ref "R28") (pin "1") (pinfunction "1_1") (pintype "passive"))
      (node (ref "VT2") (pin "2") (pinfunction "2_2") (pintype "passive"))
      (node (ref "VT3") (pin "2") (pinfunction "2_2") (pintype "passive"))
    )
    (net (code "7") (name "GND") (class "Default")
      (node (ref "C10") (pin "1") (pinfunction "1_1") (pintype "passive"))
      (node (ref "C11") (pin "1") (pinfunction "1_1") (pintype "passive"))
      (node (ref "C12") (pin "1") (pinfunction "1_1") (pintype "passive"))
      (node (ref "C14") (pin "1") (pinfunction "1_1") (pintype "passive"))
      (node (ref "C15") (pin "1") (pinfunction "1_1") (pintype "passive"))
      (node (ref "C16") (pin "1") (pinfunction "1_1") (pintype "passive"))
      (node (ref "C17") (pin "2") (pinfunction "2_2") (pintype "passive"))
      (node (ref "C18") (pin "1") (pinfunction "1_1") (pintype "passive"))
      (node (ref "C2") (pin "1") (pinfunction "1_1") (pintype "passive"))
      (node (ref "C23") (pin "1") (pinfunction "1_1") (pintype "passive"))
      (node (ref "C24") (pin "1") (pinfunction "1_1") (pintype "passive"))
      (node (ref "C25") (pin "1") (pinfunction "1_1") (pintype "passive"))
      (node (ref "C26") (pin "1") (pinfunction "1_1") (pintype "passive"))
      (node (ref "C3") (pin "1") (pinfunction "1_1") (pintype "passive"))
      (node (ref "C4") (pin "1") (pinfunction "1_1") (pintype "passive"))
      (node (ref "C5") (pin "1") (pinfunction "1_1") (pintype "passive"))
      (node (ref "C6") (pin "1") (pinfunction "1_1") (pintype "passive"))
      (node (ref "C7") (pin "1") (pinfunction "1_1") (pintype "passive"))
      (node (ref "C8") (pin "1") (pinfunction "1_1") (pintype "passive"))
      (node (ref "C9") (pin "2") (pinfunction "2_2") (pintype "passive"))
      (node (ref "DA1") (pin "4") (pinfunction "V-_4") (pintype "power_in"))
      (node (ref "DD1") (pin "6") (pinfunction "GND_6") (pintype "passive"))
      (node (ref "DD2") (pin "6") (pinfunction "GND_6") (pintype "passive"))
      (node (ref "DD3") (pin "3") (pinfunction "GND_3") (pintype "power_in"))
      (node (ref "L5") (pin "2") (pinfunction "2_2") (pintype "passive"))
      (node (ref "L6") (pin "2") (pinfunction "2_2") (pintype "passive"))
      (node (ref "R20") (pin "2") (pinfunction "2_2") (pintype "passive"))
      (node (ref "R21") (pin "1") (pinfunction "1_1") (pintype "passive"))
      (node (ref "R4") (pin "1") (pinfunction "1_1") (pintype "passive"))
      (node (ref "R6") (pin "1") (pinfunction "1_1") (pintype "passive"))
      (node (ref "R9") (pin "1") (pinfunction "1_1") (pintype "passive"))
      (node (ref "VD1") (pin "2") (pinfunction "A_2") (pintype "passive"))
      (node (ref "VD2") (pin "2") (pinfunction "A_2") (pintype "passive"))
      (node (ref "VD3") (pin "1") (pinfunction "K_1") (pintype "passive"))
      (node (ref "VD4") (pin "1") (pinfunction "K_1") (pintype "passive"))
      (node (ref "VD5") (pin "2") (pinfunction "A_2") (pintype "passive"))
      (node (ref "VD6") (pin "1") (pinfunction "K_1") (pintype "passive"))
      (node (ref "VT3") (pin "3") (pinfunction "3_3") (pintype "passive"))
      (node (ref "X1") (pin "2") (pinfunction "2_2") (pintype "passive"))
      (node (ref "X2") (pin "2") (pinfunction "2_2") (pintype "passive"))
      (node (ref "X3") (pin "5") (pinfunction "5_5") (pintype "passive"))
    )
    (net (code "8") (name "Net-(C30-Pad2)") (class "Default")
      (node (ref "C30") (pin "2") (pinfunction "2_2") (pintype "passive"))
      (node (ref "C31") (pin "2") (pinfunction "2_2") (pintype "passive"))
      (node (ref "R23") (pin "2") (pinfunction "2_2") (pintype "passive"))
    )
    (net (code "9") (name "Net-(DA1-+INA)") (class "Default")
      (node (ref "DA1") (pin "3") (pinfunction "+INA_3") (pintype "power_in"))
      (node (ref "R17") (pin "1") (pinfunction "1_1") (pintype "passive"))
      (node (ref "R21") (pin "2") (pinfunction "2_2") (pintype "passive"))
    )
    (net (code "10") (name "Net-(DA1--INA)") (class "Default")
      (node (ref "DA1") (pin "2") (pinfunction "-INA_2") (pintype "power_in"))
      (node (ref "R22") (pin "2") (pinfunction "2_2") (pintype "passive"))
    )
    (net (code "11") (name "Net-(DA1-OUTA)") (class "Default")
      (node (ref "DA1") (pin "6") (pinfunction "OUTA_6") (pintype "power_in"))
      (node (ref "R19") (pin "1") (pinfunction "1_1") (pintype "passive"))
    )
    (net (code "12") (name "Net-(DA3-+IN)") (class "Default")
      (node (ref "C30") (pin "1") (pinfunction "1_1") (pintype "passive"))
      (node (ref "DA3") (pin "4") (pinfunction "+IN_4") (pintype "passive"))
      (node (ref "R24") (pin "2") (pinfunction "2_2") (pintype "passive"))
    )
    (net (code "13") (name "Net-(DA3-+RG)") (class "Default")
      (node (ref "DA3") (pin "2") (pinfunction "+RG_2") (pintype "passive"))
      (node (ref "R26") (pin "1") (pinfunction "1_1") (pintype "passive"))
    )
    (net (code "14") (name "Net-(DA3-+Vs)") (class "Default")
      (node (ref "C32") (pin "2") (pinfunction "2_2") (pintype "passive"))
      (node (ref "C33") (pin "2") (pinfunction "2_2") (pintype "passive"))
      (node (ref "DA3") (pin "8") (pinfunction "+Vs_8") (pintype "passive"))
      (node (ref "L3") (pin "1") (pinfunction "1_1") (pintype "passive"))
    )
    (net (code "15") (name "Net-(DA3--IN)") (class "Default")
      (node (ref "C35") (pin "1") (pinfunction "1_1") (pintype "passive"))
      (node (ref "DA3") (pin "1") (pinfunction "-IN_1") (pintype "passive"))
      (node (ref "R25") (pin "2") (pinfunction "2_2") (pintype "passive"))
    )
    (net (code "16") (name "Net-(DA3--RG)") (class "Default")
      (node (ref "DA3") (pin "3") (pinfunction "-RG_3") (pintype "passive"))
      (node (ref "R26") (pin "2") (pinfunction "2_2") (pintype "passive"))
    )
    (net (code "17") (name "Net-(DA3--Vs)") (class "Default")
      (node (ref "C39") (pin "1") (pinfunction "1_1") (pintype "passive"))
      (node (ref "C40") (pin "1") (pinfunction "1_1") (pintype "passive"))
      (node (ref "DA3") (pin "5") (pinfunction "-Vs_5") (pintype "passive"))
      (node (ref "L5") (pin "1") (pinfunction "1_1") (pintype "passive"))
    )
    (net (code "18") (name "Net-(DA3-OUT)") (class "Default")
      (node (ref "DA3") (pin "7") (pinfunction "OUT_7") (pintype "passive"))
      (node (ref "R15") (pin "1") (pinfunction "1_1") (pintype "passive"))
    )
    (net (code "19") (name "Net-(DA5-+IN)") (class "Default")
      (node (ref "C34") (pin "1") (pinfunction "1_1") (pintype "passive"))
      (node (ref "DA5") (pin "4") (pinfunction "+IN_4") (pintype "passive"))
      (node (ref "R27") (pin "1") (pinfunction "1_1") (pintype "passive"))
      (node (ref "X4") (pin "1") (pinfunction "1_1") (pintype "passive"))
    )
    (net (code "20") (name "Net-(DA5-+RG)") (class "Default")
      (node (ref "DA5") (pin "2") (pinfunction "+RG_2") (pintype "passive"))
      (node (ref "R29") (pin "1") (pinfunction "1_1") (pintype "passive"))
    )
    (net (code "21") (name "Net-(DA5-+Vs)") (class "Default")
      (node (ref "C42") (pin "2") (pinfunction "2_2") (pintype "passive"))
      (node (ref "C43") (pin "2") (pinfunction "2_2") (pintype "passive"))
      (node (ref "DA5") (pin "8") (pinfunction "+Vs_8") (pintype "passive"))
      (node (ref "L4") (pin "1") (pinfunction "1_1") (pintype "passive"))
    )
    (net (code "22") (name "Net-(DA5--IN)") (class "Default")
      (node (ref "C41") (pin "2") (pinfunction "2_2") (pintype "passive"))
      (node (ref "DA5") (pin "1") (pinfunction "-IN_1") (pintype "passive"))
      (node (ref "R28") (pin "2") (pinfunction "2_2") (pintype "passive"))
      (node (ref "X4") (pin "2") (pinfunction "2_2") (pintype "passive"))
    )
    (net (code "23") (name "Net-(DA5--RG)") (class "Default")
      (node (ref "DA5") (pin "3") (pinfunction "-RG_3") (pintype "passive"))
      (node (ref "R29") (pin "2") (pinfunction "2_2") (pintype "passive"))
    )
    (net (code "24") (name "Net-(DA5--Vs)") (class "Default")
      (node (ref "C44") (pin "1") (pinfunction "1_1") (pintype "passive"))
      (node (ref "C45") (pin "1") (pinfunction "1_1") (pintype "passive"))
      (node (ref "DA5") (pin "5") (pinfunction "-Vs_5") (pintype "passive"))
      (node (ref "L6") (pin "1") (pinfunction "1_1") (pintype "passive"))
    )
    (net (code "25") (name "Net-(DA5-OUT)") (class "Default")
      (node (ref "DA5") (pin "7") (pinfunction "OUT_7") (pintype "passive"))
      (node (ref "R14") (pin "1") (pinfunction "1_1") (pintype "passive"))
      (node (ref "R23") (pin "1") (pinfunction "1_1") (pintype "passive"))
    )
    (net (code "26") (name "Net-(DD1-BOOT)") (class "Default")
      (node (ref "C1") (pin "2") (pinfunction "2_2") (pintype "passive"))
      (node (ref "DD1") (pin "1") (pinfunction "BOOT_1") (pintype "passive"))
    )
    (net (code "27") (name "Net-(DD1-PH)") (class "Default")
      (node (ref "C1") (pin "1") (pinfunction "1_1") (pintype "passive"))
      (node (ref "DD1") (pin "8") (pinfunction "PH_8") (pintype "passive"))
      (node (ref "L1") (pin "1") (pinfunction "1_1") (pintype "passive"))
      (node (ref "VD2") (pin "1") (pinfunction "K_1") (pintype "passive"))
    )
    (net (code "28") (name "Net-(DD1-SEN)") (class "Default")
      (node (ref "DD1") (pin "4") (pinfunction "SEN_4") (pintype "passive"))
      (node (ref "R2") (pin "1") (pinfunction "1_1") (pintype "passive"))
      (node (ref "R5") (pin "2") (pinfunction "2_2") (pintype "passive"))
    )
    (net (code "29") (name "Net-(DD2-BOOT)") (class "Default")
      (node (ref "C13") (pin "2") (pinfunction "2_2") (pintype "passive"))
      (node (ref "DD2") (pin "1") (pinfunction "BOOT_1") (pintype "passive"))
    )
    (net (code "30") (name "Net-(DD2-PH)") (class "Default")
      (node (ref "C13") (pin "1") (pinfunction "1_1") (pintype "passive"))
      (node (ref "DD2") (pin "8") (pinfunction "PH_8") (pintype "passive"))
      (node (ref "L2") (pin "1") (pinfunction "1_1") (pintype "passive"))
      (node (ref "VD5") (pin "1") (pinfunction "K_1") (pintype "passive"))
    )
    (net (code "31") (name "Net-(DD2-SEN)") (class "Default")
      (node (ref "DD2") (pin "4") (pinfunction "SEN_4") (pintype "passive"))
      (node (ref "R7") (pin "1") (pinfunction "1_1") (pintype "passive"))
      (node (ref "R9") (pin "2") (pinfunction "2_2") (pintype "passive"))
    )
    (net (code "32") (name "Net-(DD3-AIN0)") (class "Default")
      (node (ref "C19") (pin "2") (pinfunction "2_2") (pintype "passive"))
      (node (ref "DD3") (pin "4") (pinfunction "AIN0_4") (pintype "power_in"))
      (node (ref "R14") (pin "2") (pinfunction "2_2") (pintype "passive"))
    )
    (net (code "33") (name "Net-(DD3-AIN1)") (class "Default")
      (node (ref "C20") (pin "2") (pinfunction "2_2") (pintype "passive"))
      (node (ref "DD3") (pin "5") (pinfunction "AIN1_5") (pintype "power_in"))
      (node (ref "R15") (pin "2") (pinfunction "2_2") (pintype "passive"))
    )
    (net (code "34") (name "Net-(DD3-ALERT{slash}RDY)") (class "Default")
      (node (ref "DD3") (pin "2") (pinfunction "ALERT/RDY_2") (pintype "power_in"))
      (node (ref "R12") (pin "1") (pinfunction "1_1") (pintype "passive"))
      (node (ref "R18") (pin "1") (pinfunction "1_1") (pintype "passive"))
    )
    (net (code "35") (name "Net-(DD3-SCL)") (class "Default")
      (node (ref "DD3") (pin "10") (pinfunction "SCL_10") (pintype "power_in"))
      (node (ref "R11") (pin "1") (pinfunction "1_1") (pintype "passive"))
      (node (ref "R16") (pin "1") (pinfunction "1_1") (pintype "passive"))
    )
    (net (code "36") (name "Net-(DD3-SDA)") (class "Default")
      (node (ref "DD3") (pin "9") (pinfunction "SDA_9") (pintype "power_in"))
      (node (ref "R10") (pin "1") (pinfunction "1_1") (pintype "passive"))
      (node (ref "R13") (pin "1") (pinfunction "1_1") (pintype "passive"))
    )
    (net (code "37") (name "Net-(R5-Pad1)") (class "Default")
      (node (ref "R5") (pin "1") (pinfunction "1_1") (pintype "passive"))
      (node (ref "R6") (pin "2") (pinfunction "2_2") (pintype "passive"))
    )
    (net (code "38") (name "Net-(R13-Pad2)") (class "Default")
      (node (ref "R13") (pin "2") (pinfunction "2_2") (pintype "passive"))
      (node (ref "X3") (pin "2") (pinfunction "2_2") (pintype "passive"))
    )
    (net (code "39") (name "Net-(R16-Pad2)") (class "Default")
      (node (ref "R16") (pin "2") (pinfunction "2_2") (pintype "passive"))
      (node (ref "X3") (pin "3") (pinfunction "3_3") (pintype "passive"))
    )
    (net (code "40") (name "Net-(R18-Pad2)") (class "Default")
      (node (ref "R18") (pin "2") (pinfunction "2_2") (pintype "passive"))
      (node (ref "X3") (pin "4") (pinfunction "4_4") (pintype "passive"))
    )
    (net (code "41") (name "Net-(R19-Pad2)") (class "Default")
      (node (ref "R19") (pin "2") (pinfunction "2_2") (pintype "passive"))
      (node (ref "VT2") (pin "1") (pinfunction "1_1") (pintype "passive"))
      (node (ref "VT3") (pin "1") (pinfunction "1_1") (pintype "passive"))
    )
    (net (code "42") (name "Net-(VD3-A)") (class "Default")
      (node (ref "R1") (pin "1") (pinfunction "1_1") (pintype "passive"))
      (node (ref "VD3") (pin "2") (pinfunction "A_2") (pintype "passive"))
    )
    (net (code "43") (name "Net-(VD4-A)") (class "Default")
      (node (ref "R3") (pin "1") (pinfunction "1_1") (pintype "passive"))
      (node (ref "VD4") (pin "2") (pinfunction "A_2") (pintype "passive"))
    )
    (net (code "44") (name "Net-(VD6-A)") (class "Default")
      (node (ref "R8") (pin "1") (pinfunction "1_1") (pintype "passive"))
      (node (ref "VD6") (pin "2") (pinfunction "A_2") (pintype "passive"))
    )
    (net (code "45") (name "Net-(VD7-K)") (class "Default")
      (node (ref "VD7") (pin "1") (pinfunction "K_1") (pintype "passive"))
      (node (ref "X3") (pin "1") (pinfunction "1_1") (pintype "passive"))
    )
    (net (code "46") (name "Net-(VT1-D)") (class "Default")
      (node (ref "VT1") (pin "2") (pinfunction "D_2") (pintype "passive"))
      (node (ref "X1") (pin "1") (pinfunction "1_1") (pintype "passive"))
      (node (ref "X2") (pin "1") (pinfunction "1_1") (pintype "passive"))
    )
    (net (code "47") (name "Net-(VT1-G)") (class "Default")
      (node (ref "R4") (pin "2") (pinfunction "2_2") (pintype "passive"))
      (node (ref "VT1") (pin "1") (pinfunction "G_1") (pintype "passive"))
    )
    (net (code "48") (name "unconnected-(DA1-DNC-Pad1)") (class "Default")
      (node (ref "DA1") (pin "1") (pinfunction "DNC_1") (pintype "power_in+no_connect"))
    )
    (net (code "49") (name "unconnected-(DA1-DNC-Pad5)") (class "Default")
      (node (ref "DA1") (pin "5") (pinfunction "DNC_5") (pintype "power_in+no_connect"))
    )
    (net (code "50") (name "unconnected-(DA1-NC-Pad8)") (class "Default")
      (node (ref "DA1") (pin "8") (pinfunction "NC_8") (pintype "power_in+no_connect"))
    )
    (net (code "51") (name "unconnected-(DD1-ENA-Pad5)") (class "Default")
      (node (ref "DD1") (pin "5") (pinfunction "ENA_5") (pintype "passive+no_connect"))
    )
    (net (code "52") (name "unconnected-(DD1-NC-Pad2)") (class "Default")
      (node (ref "DD1") (pin "2") (pinfunction "NC_2") (pintype "passive+no_connect"))
    )
    (net (code "53") (name "unconnected-(DD1-NC-Pad3)") (class "Default")
      (node (ref "DD1") (pin "3") (pinfunction "NC_3") (pintype "passive+no_connect"))
    )
    (net (code "54") (name "unconnected-(DD2-ENA-Pad5)") (class "Default")
      (node (ref "DD2") (pin "5") (pinfunction "ENA_5") (pintype "passive+no_connect"))
    )
    (net (code "55") (name "unconnected-(DD2-NC-Pad2)") (class "Default")
      (node (ref "DD2") (pin "2") (pinfunction "NC_2") (pintype "passive+no_connect"))
    )
    (net (code "56") (name "unconnected-(DD2-NC-Pad3)") (class "Default")
      (node (ref "DD2") (pin "3") (pinfunction "NC_3") (pintype "passive+no_connect"))
    )
    (net (code "57") (name "unconnected-(DD3-AIN2-Pad6)") (class "Default")
      (node (ref "DD3") (pin "6") (pinfunction "AIN2_6") (pintype "power_in"))
    )
    (net (code "58") (name "unconnected-(DD3-AIN3-Pad7)") (class "Default")
      (node (ref "DD3") (pin "7") (pinfunction "AIN3_7") (pintype "power_in"))
    )
  )
)
